# Sheet1.net
KiCad netlist of a schematic drawn in Altium Designer
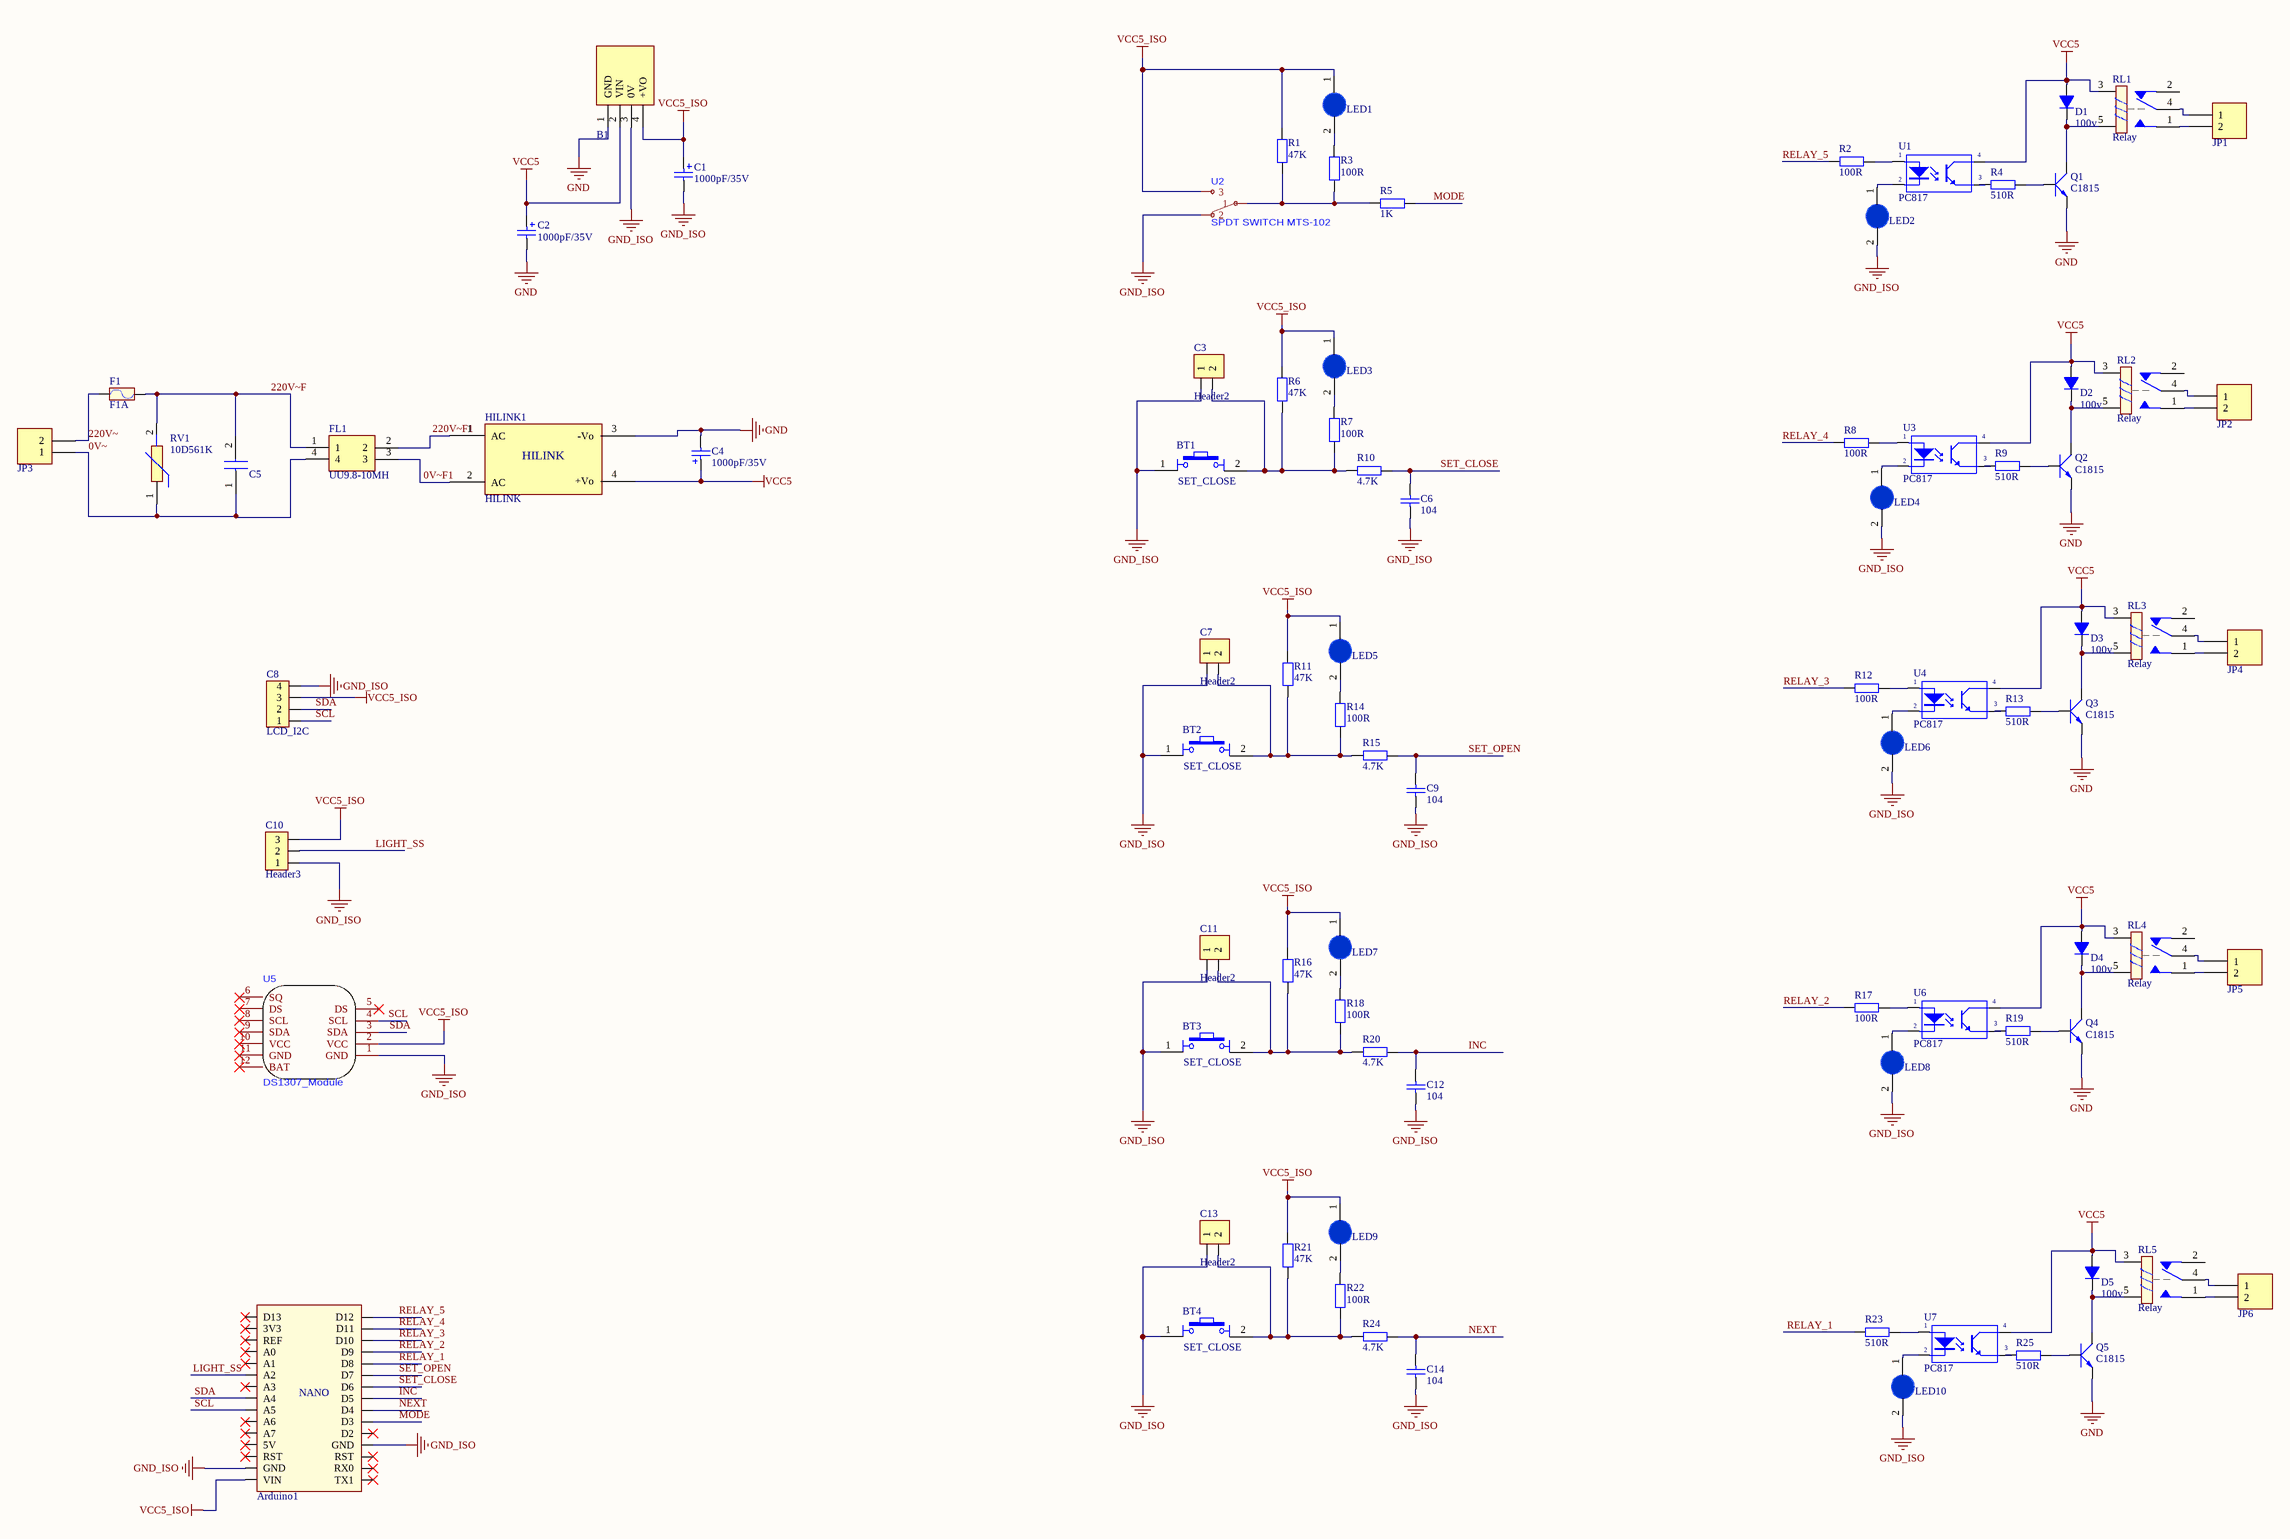
[diagram p0: Sheet1.SchDoc]

(export (version "E")
  (design (tool "Eeschema 10.0.6"))
  (components
    (comp (ref "Arduino1")
      (value "Arduino Nano")
      (footprint "Arduino Nano")
      (description "Arduino NANO")
      (libsource (lib "myLib_v1") (part "Arduino Nano"))
    )
    (comp (ref "B1")
      (value "B0505S1W")
      (footprint "B0505S1W")
      (description "Power Supply")
      (fields (field (name "MANUFACTURER_PART_NUMBER") "B0505S-1W"))
      (libsource (lib "myLib_v1") (part "B0505S1W"))
    )
    (comp (ref "BT1")
      (value "SET_CLOSE")
      (footprint "Nut Nhan 4 Chan Cam 6x6")
      (description "Nut Nhan 4 Chan 6x6mm")
      (libsource (lib "Altium_Lib_by_KhueNguyenCreator") (part "Nut Nhan 4 Chan Cam 6x6"))
    )
    (comp (ref "BT2")
      (value "SET_CLOSE")
      (footprint "Nut Nhan 4 Chan Cam 6x6")
      (description "Nut Nhan 4 Chan 6x6mm")
      (libsource (lib "Altium_Lib_by_KhueNguyenCreator") (part "Nut Nhan 4 Chan Cam 6x6"))
    )
    (comp (ref "BT3")
      (value "SET_CLOSE")
      (footprint "Nut Nhan 4 Chan Cam 6x6")
      (description "Nut Nhan 4 Chan 6x6mm")
      (libsource (lib "Altium_Lib_by_KhueNguyenCreator") (part "Nut Nhan 4 Chan Cam 6x6"))
    )
    (comp (ref "BT4")
      (value "SET_CLOSE")
      (footprint "Nut Nhan 4 Chan Cam 6x6")
      (description "Nut Nhan 4 Chan 6x6mm")
      (libsource (lib "Altium_Lib_by_KhueNguyenCreator") (part "Nut Nhan 4 Chan Cam 6x6"))
    )
    (comp (ref "C1")
      (value "1000pF/35V")
      (footprint "CP2/5")
      (description "Polarized Capacitor (Surface Mount)")
      (fields (field (name "Comment") "Cap Pol3") (field (name "PUBLISHER") "Altium Limited"))
      (libsource (lib "myLib_v1") (part "Cap Pol3"))
    )
    (comp (ref "C2")
      (value "1000pF/35V")
      (footprint "CP2/5")
      (description "Polarized Capacitor (Surface Mount)")
      (fields (field (name "Comment") "Cap Pol3") (field (name "PUBLISHER") "Altium Limited"))
      (libsource (lib "myLib_v1") (part "Cap Pol3"))
    )
    (comp (ref "C3")
      (value "Header2")
      (footprint "Header2")
      (description "Header IDC, 2 x 1 Pin Vertical 2.54mm Pitch (Non-Boxed, Male)")
      (fields
        (field (name "MANUFACTURER") "Würth Elektronik eiSos GmbH")
        (field (name "PARTNO") "613002143121")
        (field (name "CREATED BY") "Karrer Zheng")
      )
      (libsource (lib "myLib_v1") (part "Header2"))
    )
    (comp (ref "C4")
      (value "1000pF/35V")
      (footprint "CP2/5")
      (description "Polarized Capacitor (Surface Mount)")
      (fields (field (name "Comment") "Cap Pol3") (field (name "PUBLISHER") "Altium Limited"))
      (libsource (lib "myLib_v1") (part "Cap Pol3"))
    )
    (comp (ref "C5")
      (value "R46KF3100JMP0K")
      (footprint "R46KF3100JMP0K")
      (description "Capacitor")
      (fields (field (name "MOUSER PART NUMBER") "80-R46KF3100JMP0K"))
      (libsource (lib "myLib_v1") (part "R46KF3100JMP0K"))
    )
    (comp (ref "C6")
      (value "104")
      (footprint "tu gom")
      (description "Cắm")
      (libsource (lib "Altium_Lib_by_KhueNguyenCreator") (part "Tu gom 104 50V"))
    )
    (comp (ref "C7")
      (value "Header2")
      (footprint "Header2")
      (description "Header IDC, 2 x 1 Pin Vertical 2.54mm Pitch (Non-Boxed, Male)")
      (fields
        (field (name "MANUFACTURER") "Würth Elektronik eiSos GmbH")
        (field (name "PARTNO") "613002143121")
        (field (name "CREATED BY") "Karrer Zheng")
      )
      (libsource (lib "myLib_v1") (part "Header2"))
    )
    (comp (ref "C8")
      (value "LCD_I2C")
      (footprint "Header4")
      (description "Header IDC, 4 x 1 Pin Vertical 2.54mm Pitch (Non-Boxed, Male)")
      (fields
        (field (name "MANUFACTURER") "Würth Elektronik eiSos GmbH")
        (field (name "PARTNO") "613002143121")
        (field (name "CREATED BY") "Karrer Zheng")
      )
      (libsource (lib "myLib_v1") (part "Header4"))
    )
    (comp (ref "C9")
      (value "104")
      (footprint "tu gom")
      (description "Cắm")
      (libsource (lib "Altium_Lib_by_KhueNguyenCreator") (part "Tu gom 104 50V"))
    )
    (comp (ref "C10")
      (value "Header3")
      (footprint "Header3")
      (description "Header IDC, 3 x 1 Pin Vertical 2.54mm Pitch (Non-Boxed, Male)")
      (fields
        (field (name "MANUFACTURER") "Würth Elektronik eiSos GmbH")
        (field (name "PARTNO") "613002143121")
        (field (name "CREATED BY") "Karrer Zheng")
      )
      (libsource (lib "myLib_v1") (part "Header3"))
    )
    (comp (ref "C11")
      (value "Header2")
      (footprint "Header2")
      (description "Header IDC, 2 x 1 Pin Vertical 2.54mm Pitch (Non-Boxed, Male)")
      (fields
        (field (name "MANUFACTURER") "Würth Elektronik eiSos GmbH")
        (field (name "PARTNO") "613002143121")
        (field (name "CREATED BY") "Karrer Zheng")
      )
      (libsource (lib "myLib_v1") (part "Header2"))
    )
    (comp (ref "C12")
      (value "104")
      (footprint "tu gom")
      (description "Cắm")
      (libsource (lib "Altium_Lib_by_KhueNguyenCreator") (part "Tu gom 104 50V"))
    )
    (comp (ref "C13")
      (value "Header2")
      (footprint "Header2")
      (description "Header IDC, 2 x 1 Pin Vertical 2.54mm Pitch (Non-Boxed, Male)")
      (fields
        (field (name "MANUFACTURER") "Würth Elektronik eiSos GmbH")
        (field (name "PARTNO") "613002143121")
        (field (name "CREATED BY") "Karrer Zheng")
      )
      (libsource (lib "myLib_v1") (part "Header2"))
    )
    (comp (ref "C14")
      (value "104")
      (footprint "tu gom")
      (description "Cắm")
      (libsource (lib "Altium_Lib_by_KhueNguyenCreator") (part "Tu gom 104 50V"))
    )
    (comp (ref "D1")
      (value "100v")
      (footprint "DIODE 0.5A")
      (description "Cắm")
      (libsource (lib "Altium_Lib_by_KhueNguyenCreator") (part "Diode 1N4148"))
    )
    (comp (ref "D2")
      (value "100v")
      (footprint "DIODE 0.5A")
      (description "Cắm")
      (libsource (lib "Altium_Lib_by_KhueNguyenCreator") (part "Diode 1N4148"))
    )
    (comp (ref "D3")
      (value "100v")
      (footprint "DIODE 0.5A")
      (description "Cắm")
      (libsource (lib "Altium_Lib_by_KhueNguyenCreator") (part "Diode 1N4148"))
    )
    (comp (ref "D4")
      (value "100v")
      (footprint "DIODE 0.5A")
      (description "Cắm")
      (libsource (lib "Altium_Lib_by_KhueNguyenCreator") (part "Diode 1N4148"))
    )
    (comp (ref "D5")
      (value "100v")
      (footprint "DIODE 0.5A")
      (description "Cắm")
      (libsource (lib "Altium_Lib_by_KhueNguyenCreator") (part "Diode 1N4148"))
    )
    (comp (ref "F1")
      (value "F1A")
      (footprint "Fuse")
      (description "Fuse")
      (fields (field (name "DESIGNED BY") "VanDungEvn"))
      (libsource (lib "myLib_v1") (part "Fuse"))
    )
    (comp (ref "FL1")
      (value "UU9.8-10MH")
      (footprint "UU9810MH")
      (description "Filter")
      (libsource (lib "myLib_v1") (part "UU9.8-10MH"))
    )
    (comp (ref "HILINK1")
      (value "HILINK")
      (footprint "HILINK_1W")
      (libsource (lib "myLib_v1") (part "HILINK"))
    )
    (comp (ref "JP1")
      (value "Header 2_1")
      (footprint "HED2")
      (description "Header, 2-Pin")
      (fields (field (name "MANUFACTURER") "Generic Components"))
      (libsource (lib "myLib_v1") (part "Header 2_1"))
    )
    (comp (ref "JP2")
      (value "Header 2_1")
      (footprint "HED2")
      (description "Header, 2-Pin")
      (fields (field (name "MANUFACTURER") "Generic Components"))
      (libsource (lib "myLib_v1") (part "Header 2_1"))
    )
    (comp (ref "JP3")
      (value "Header 2_1")
      (footprint "HED2")
      (description "Header, 2-Pin")
      (fields (field (name "MANUFACTURER") "Generic Components"))
      (libsource (lib "") (part "Header 2_1_1"))
    )
    (comp (ref "JP4")
      (value "Header 2_1")
      (footprint "HED2")
      (description "Header, 2-Pin")
      (fields (field (name "MANUFACTURER") "Generic Components"))
      (libsource (lib "myLib_v1") (part "Header 2_1"))
    )
    (comp (ref "JP5")
      (value "Header 2_1")
      (footprint "HED2")
      (description "Header, 2-Pin")
      (fields (field (name "MANUFACTURER") "Generic Components"))
      (libsource (lib "myLib_v1") (part "Header 2_1"))
    )
    (comp (ref "JP6")
      (value "Header 2_1")
      (footprint "HED2")
      (description "Header, 2-Pin")
      (fields (field (name "MANUFACTURER") "Generic Components"))
      (libsource (lib "myLib_v1") (part "Header 2_1"))
    )
    (comp (ref "LED1")
      (value "LED 3mm")
      (footprint "LED-3MM-BLUE")
      (description "Cắm")
      (libsource (lib "myLib_v1") (part "LED 3mm Xanh Duong"))
    )
    (comp (ref "LED2")
      (value "LED 3mm")
      (footprint "LED-3MM-BLUE")
      (description "Cắm")
      (libsource (lib "myLib_v1") (part "LED 3mm Xanh Duong"))
    )
    (comp (ref "LED3")
      (value "LED 3mm")
      (footprint "LED-3MM-BLUE")
      (description "Cắm")
      (libsource (lib "myLib_v1") (part "LED 3mm Xanh Duong"))
    )
    (comp (ref "LED4")
      (value "LED 3mm")
      (footprint "LED-3MM-BLUE")
      (description "Cắm")
      (libsource (lib "myLib_v1") (part "LED 3mm Xanh Duong"))
    )
    (comp (ref "LED5")
      (value "LED 3mm")
      (footprint "LED-3MM-BLUE")
      (description "Cắm")
      (libsource (lib "myLib_v1") (part "LED 3mm Xanh Duong"))
    )
    (comp (ref "LED6")
      (value "LED 3mm")
      (footprint "LED-3MM-BLUE")
      (description "Cắm")
      (libsource (lib "myLib_v1") (part "LED 3mm Xanh Duong"))
    )
    (comp (ref "LED7")
      (value "LED 3mm")
      (footprint "LED-3MM-BLUE")
      (description "Cắm")
      (libsource (lib "myLib_v1") (part "LED 3mm Xanh Duong"))
    )
    (comp (ref "LED8")
      (value "LED 3mm")
      (footprint "LED-3MM-BLUE")
      (description "Cắm")
      (libsource (lib "myLib_v1") (part "LED 3mm Xanh Duong"))
    )
    (comp (ref "LED9")
      (value "LED 3mm")
      (footprint "LED-3MM-BLUE")
      (description "Cắm")
      (libsource (lib "myLib_v1") (part "LED 3mm Xanh Duong"))
    )
    (comp (ref "LED10")
      (value "LED 3mm")
      (footprint "LED-3MM-BLUE")
      (description "Cắm")
      (libsource (lib "myLib_v1") (part "LED 3mm Xanh Duong"))
    )
    (comp (ref "Q1")
      (value "C1815")
      (footprint "C1815_cam")
      (description "NPN 600mW, ECB")
      (libsource (lib "myLib_v1") (part "C1815"))
    )
    (comp (ref "Q2")
      (value "C1815")
      (footprint "C1815_cam")
      (description "NPN 600mW, ECB")
      (libsource (lib "myLib_v1") (part "C1815"))
    )
    (comp (ref "Q3")
      (value "C1815")
      (footprint "C1815_cam")
      (description "NPN 600mW, ECB")
      (libsource (lib "myLib_v1") (part "C1815"))
    )
    (comp (ref "Q4")
      (value "C1815")
      (footprint "C1815_cam")
      (description "NPN 600mW, ECB")
      (libsource (lib "myLib_v1") (part "C1815"))
    )
    (comp (ref "Q5")
      (value "C1815")
      (footprint "C1815_cam")
      (description "NPN 600mW, ECB")
      (libsource (lib "myLib_v1") (part "C1815"))
    )
    (comp (ref "R1")
      (value "47K")
      (footprint "R1/4W")
      (description "Resistor 1/4W")
      (libsource (lib "myLib_v1") (part "R1/4W"))
    )
    (comp (ref "R2")
      (value "100R")
      (footprint "R1/4W")
      (description "Resistor 1/4W")
      (libsource (lib "myLib_v1") (part "R1/4W"))
    )
    (comp (ref "R3")
      (value "100R")
      (footprint "R1/4W")
      (description "Resistor 1/4W")
      (libsource (lib "myLib_v1") (part "R1/4W"))
    )
    (comp (ref "R4")
      (value "510R")
      (footprint "R1/4W")
      (description "Resistor 1/4W")
      (libsource (lib "myLib_v1") (part "R1/4W"))
    )
    (comp (ref "R5")
      (value "1K")
      (footprint "R1/4W")
      (description "Resistor 1/4W")
      (libsource (lib "myLib_v1") (part "R1/4W"))
    )
    (comp (ref "R6")
      (value "47K")
      (footprint "R1/4W")
      (description "Resistor 1/4W")
      (libsource (lib "myLib_v1") (part "R1/4W"))
    )
    (comp (ref "R7")
      (value "100R")
      (footprint "R1/4W")
      (description "Resistor 1/4W")
      (libsource (lib "myLib_v1") (part "R1/4W"))
    )
    (comp (ref "R8")
      (value "100R")
      (footprint "R1/4W")
      (description "Resistor 1/4W")
      (libsource (lib "myLib_v1") (part "R1/4W"))
    )
    (comp (ref "R9")
      (value "510R")
      (footprint "R1/4W")
      (description "Resistor 1/4W")
      (libsource (lib "myLib_v1") (part "R1/4W"))
    )
    (comp (ref "R10")
      (value "4.7K")
      (footprint "R1/4W")
      (description "Resistor 1/4W")
      (libsource (lib "myLib_v1") (part "R1/4W"))
    )
    (comp (ref "R11")
      (value "47K")
      (footprint "R1/4W")
      (description "Resistor 1/4W")
      (libsource (lib "myLib_v1") (part "R1/4W"))
    )
    (comp (ref "R12")
      (value "100R")
      (footprint "R1/4W")
      (description "Resistor 1/4W")
      (libsource (lib "myLib_v1") (part "R1/4W"))
    )
    (comp (ref "R13")
      (value "510R")
      (footprint "R1/4W")
      (description "Resistor 1/4W")
      (libsource (lib "myLib_v1") (part "R1/4W"))
    )
    (comp (ref "R14")
      (value "100R")
      (footprint "R1/4W")
      (description "Resistor 1/4W")
      (libsource (lib "myLib_v1") (part "R1/4W"))
    )
    (comp (ref "R15")
      (value "4.7K")
      (footprint "R1/4W")
      (description "Resistor 1/4W")
      (libsource (lib "myLib_v1") (part "R1/4W"))
    )
    (comp (ref "R16")
      (value "47K")
      (footprint "R1/4W")
      (description "Resistor 1/4W")
      (libsource (lib "myLib_v1") (part "R1/4W"))
    )
    (comp (ref "R17")
      (value "100R")
      (footprint "R1/4W")
      (description "Resistor 1/4W")
      (libsource (lib "myLib_v1") (part "R1/4W"))
    )
    (comp (ref "R18")
      (value "100R")
      (footprint "R1/4W")
      (description "Resistor 1/4W")
      (libsource (lib "myLib_v1") (part "R1/4W"))
    )
    (comp (ref "R19")
      (value "510R")
      (footprint "R1/4W")
      (description "Resistor 1/4W")
      (libsource (lib "myLib_v1") (part "R1/4W"))
    )
    (comp (ref "R20")
      (value "4.7K")
      (footprint "R1/4W")
      (description "Resistor 1/4W")
      (libsource (lib "myLib_v1") (part "R1/4W"))
    )
    (comp (ref "R21")
      (value "47K")
      (footprint "R1/4W")
      (description "Resistor 1/4W")
      (libsource (lib "myLib_v1") (part "R1/4W"))
    )
    (comp (ref "R22")
      (value "100R")
      (footprint "R1/4W")
      (description "Resistor 1/4W")
      (libsource (lib "myLib_v1") (part "R1/4W"))
    )
    (comp (ref "R23")
      (value "510R")
      (footprint "R1/4W")
      (description "Resistor 1/4W")
      (libsource (lib "myLib_v1") (part "R1/4W"))
    )
    (comp (ref "R24")
      (value "4.7K")
      (footprint "R1/4W")
      (description "Resistor 1/4W")
      (libsource (lib "myLib_v1") (part "R1/4W"))
    )
    (comp (ref "R25")
      (value "510R")
      (footprint "R1/4W")
      (description "Resistor 1/4W")
      (libsource (lib "myLib_v1") (part "R1/4W"))
    )
    (comp (ref "RL1")
      (value "Relay")
      (footprint "RELAY_SRA_05VDC_CL")
      (description "Relay 5 Chan")
      (libsource (lib "myLib_v1") (part "RL_SRA-05VDC-CL"))
    )
    (comp (ref "RL2")
      (value "Relay")
      (footprint "RELAY_SRA_05VDC_CL")
      (description "Relay 5 Chan")
      (libsource (lib "myLib_v1") (part "RL_SRA-05VDC-CL"))
    )
    (comp (ref "RL3")
      (value "Relay")
      (footprint "RELAY_SRA_05VDC_CL")
      (description "Relay 5 Chan")
      (libsource (lib "myLib_v1") (part "RL_SRA-05VDC-CL"))
    )
    (comp (ref "RL4")
      (value "Relay")
      (footprint "RELAY_SRA_05VDC_CL")
      (description "Relay 5 Chan")
      (libsource (lib "myLib_v1") (part "RL_SRA-05VDC-CL"))
    )
    (comp (ref "RL5")
      (value "Relay")
      (footprint "RELAY_SRA_05VDC_CL")
      (description "Relay 5 Chan")
      (libsource (lib "myLib_v1") (part "RL_SRA-05VDC-CL"))
    )
    (comp (ref "RV1")
      (value "10D561K")
      (footprint "10D561K")
      (description "Varistor")
      (fields
        (field (name "MANUFACTURER_PART_NUMBER") "MOV-10D561K")
        (field (name "MOUSER PART NUMBER") "652-MOV-10D561K")
      )
      (libsource (lib "myLib_v1") (part "10D561K"))
    )
    (comp (ref "U1")
      (value "PC817")
      (footprint "DIP4/W0.3")
      (description "Single Opto")
      (libsource (lib "myLib_v1") (part "PC817"))
    )
    (comp (ref "U2")
      (value "SPDT SWITCH MTS-102")
      (footprint "SPDT SWITCH  MTS-102")
      (libsource (lib "myLib_v1") (part "SPDT SWITCH MTS-102"))
    )
    (comp (ref "U3")
      (value "PC817")
      (footprint "DIP4/W0.3")
      (description "Single Opto")
      (libsource (lib "myLib_v1") (part "PC817"))
    )
    (comp (ref "U4")
      (value "PC817")
      (footprint "DIP4/W0.3")
      (description "Single Opto")
      (libsource (lib "myLib_v1") (part "PC817"))
    )
    (comp (ref "U5")
      (value "DS1307_Module")
      (footprint "DS1307 MODULE")
      (libsource (lib "myLib_v1") (part "DS1307_Module"))
    )
    (comp (ref "U6")
      (value "PC817")
      (footprint "DIP4/W0.3")
      (description "Single Opto")
      (libsource (lib "myLib_v1") (part "PC817"))
    )
    (comp (ref "U7")
      (value "PC817")
      (footprint "DIP4/W0.3")
      (description "Single Opto")
      (libsource (lib "myLib_v1") (part "PC817"))
    )
  )
  (nets
    (net (code "1") (name "/0V~") (class "Default")
      (node (ref "C5") (pin "1") (pinfunction "1_1") (pintype "passive"))
      (node (ref "FL1") (pin "4") (pinfunction "4_4") (pintype "passive"))
      (node (ref "JP3") (pin "1") (pinfunction "1_1") (pintype "passive"))
      (node (ref "RV1") (pin "1") (pinfunction "1_1") (pintype "passive"))
    )
    (net (code "2") (name "/0V~F1") (class "Default")
      (node (ref "FL1") (pin "3") (pinfunction "3_3") (pintype "passive"))
      (node (ref "HILINK1") (pin "2") (pinfunction "AC_2") (pintype "passive"))
    )
    (net (code "3") (name "/220V~") (class "Default")
      (node (ref "F1") (pin "1") (pinfunction "1_1") (pintype "passive"))
      (node (ref "JP3") (pin "2") (pinfunction "2_2") (pintype "passive"))
    )
    (net (code "4") (name "/220V~F") (class "Default")
      (node (ref "C5") (pin "2") (pinfunction "2_2") (pintype "passive"))
      (node (ref "F1") (pin "2") (pinfunction "2_2") (pintype "passive"))
      (node (ref "FL1") (pin "1") (pinfunction "1_1") (pintype "passive"))
      (node (ref "RV1") (pin "2") (pinfunction "2_2") (pintype "passive"))
    )
    (net (code "5") (name "/220V~F1") (class "Default")
      (node (ref "FL1") (pin "2") (pinfunction "2_2") (pintype "passive"))
      (node (ref "HILINK1") (pin "1") (pinfunction "AC_1") (pintype "passive"))
    )
    (net (code "6") (name "/INC") (class "Default")
      (node (ref "Arduino1") (pin "D5") (pinfunction "D5_D5") (pintype "passive"))
      (node (ref "C12") (pin "1") (pinfunction "1_1") (pintype "passive"))
      (node (ref "R20") (pin "1") (pinfunction "1_1") (pintype "passive"))
    )
    (net (code "7") (name "/LIGHT_SS") (class "Default")
      (node (ref "Arduino1") (pin "A2") (pinfunction "A2_A2") (pintype "passive"))
      (node (ref "C10") (pin "2") (pinfunction "2_2") (pintype "passive"))
    )
    (net (code "8") (name "/MODE") (class "Default")
      (node (ref "Arduino1") (pin "D3") (pinfunction "D3_D3") (pintype "passive"))
      (node (ref "R5") (pin "1") (pinfunction "1_1") (pintype "passive"))
    )
    (net (code "9") (name "/NEXT") (class "Default")
      (node (ref "Arduino1") (pin "D4") (pinfunction "D4_D4") (pintype "passive"))
      (node (ref "C14") (pin "1") (pinfunction "1_1") (pintype "passive"))
      (node (ref "R24") (pin "1") (pinfunction "1_1") (pintype "passive"))
    )
    (net (code "10") (name "/RELAY_1") (class "Default")
      (node (ref "Arduino1") (pin "D8") (pinfunction "D8_D8") (pintype "passive"))
      (node (ref "R23") (pin "1") (pinfunction "1_1") (pintype "passive"))
    )
    (net (code "11") (name "/RELAY_2") (class "Default")
      (node (ref "Arduino1") (pin "D9") (pinfunction "D9_D9") (pintype "passive"))
      (node (ref "R17") (pin "1") (pinfunction "1_1") (pintype "passive"))
    )
    (net (code "12") (name "/RELAY_3") (class "Default")
      (node (ref "Arduino1") (pin "D10") (pinfunction "D10_D10") (pintype "passive"))
      (node (ref "R12") (pin "1") (pinfunction "1_1") (pintype "passive"))
    )
    (net (code "13") (name "/RELAY_4") (class "Default")
      (node (ref "Arduino1") (pin "D11") (pinfunction "D11_D11") (pintype "passive"))
      (node (ref "R8") (pin "1") (pinfunction "1_1") (pintype "passive"))
    )
    (net (code "14") (name "/RELAY_5") (class "Default")
      (node (ref "Arduino1") (pin "D12") (pinfunction "D12_D12") (pintype "passive"))
      (node (ref "R2") (pin "1") (pinfunction "1_1") (pintype "passive"))
    )
    (net (code "15") (name "/SCL") (class "Default")
      (node (ref "Arduino1") (pin "A5") (pinfunction "A5_A5") (pintype "passive"))
      (node (ref "C8") (pin "1") (pinfunction "1_1") (pintype "passive"))
      (node (ref "U5") (pin "4") (pinfunction "SCL_4") (pintype "passive"))
    )
    (net (code "16") (name "/SDA") (class "Default")
      (node (ref "Arduino1") (pin "A4") (pinfunction "A4_A4") (pintype "passive"))
      (node (ref "C8") (pin "2") (pinfunction "2_2") (pintype "passive"))
      (node (ref "U5") (pin "3") (pinfunction "SDA_3") (pintype "passive"))
    )
    (net (code "17") (name "/SET_CLOSE") (class "Default")
      (node (ref "Arduino1") (pin "D6") (pinfunction "D6_D6") (pintype "passive"))
      (node (ref "C6") (pin "1") (pinfunction "1_1") (pintype "passive"))
      (node (ref "R10") (pin "1") (pinfunction "1_1") (pintype "passive"))
    )
    (net (code "18") (name "/SET_OPEN") (class "Default")
      (node (ref "Arduino1") (pin "D7") (pinfunction "D7_D7") (pintype "passive"))
      (node (ref "C9") (pin "1") (pinfunction "1_1") (pintype "passive"))
      (node (ref "R15") (pin "1") (pinfunction "1_1") (pintype "passive"))
    )
    (net (code "19") (name "GND") (class "Default")
      (node (ref "B1") (pin "1") (pinfunction "GND_1") (pintype "passive"))
      (node (ref "C2") (pin "2") (pinfunction "2_2") (pintype "passive"))
      (node (ref "C4") (pin "2") (pinfunction "2_2") (pintype "passive"))
      (node (ref "HILINK1") (pin "3") (pinfunction "-Vo_3") (pintype "passive"))
      (node (ref "Q1") (pin "1") (pinfunction "E_1") (pintype "passive"))
      (node (ref "Q2") (pin "1") (pinfunction "E_1") (pintype "passive"))
      (node (ref "Q3") (pin "1") (pinfunction "E_1") (pintype "passive"))
      (node (ref "Q4") (pin "1") (pinfunction "E_1") (pintype "passive"))
      (node (ref "Q5") (pin "1") (pinfunction "E_1") (pintype "passive"))
    )
    (net (code "20") (name "GND_ISO") (class "Default")
      (node (ref "Arduino1") (pin "GND") (pinfunction "GND_GND") (pintype "passive"))
      (node (ref "B1") (pin "3") (pinfunction "0V_3") (pintype "passive"))
      (node (ref "BT1") (pin "1") (pintype "passive"))
      (node (ref "BT2") (pin "1") (pintype "passive"))
      (node (ref "BT3") (pin "1") (pintype "passive"))
      (node (ref "BT4") (pin "1") (pintype "passive"))
      (node (ref "C1") (pin "2") (pinfunction "2_2") (pintype "passive"))
      (node (ref "C10") (pin "1") (pinfunction "1_1") (pintype "passive"))
      (node (ref "C11") (pin "1") (pinfunction "1_1") (pintype "passive"))
      (node (ref "C12") (pin "2") (pinfunction "2_2") (pintype "passive"))
      (node (ref "C13") (pin "1") (pinfunction "1_1") (pintype "passive"))
      (node (ref "C14") (pin "2") (pinfunction "2_2") (pintype "passive"))
      (node (ref "C3") (pin "1") (pinfunction "1_1") (pintype "passive"))
      (node (ref "C6") (pin "2") (pinfunction "2_2") (pintype "passive"))
      (node (ref "C7") (pin "1") (pinfunction "1_1") (pintype "passive"))
      (node (ref "C8") (pin "4") (pinfunction "4_4") (pintype "passive"))
      (node (ref "C9") (pin "2") (pinfunction "2_2") (pintype "passive"))
      (node (ref "LED10") (pin "2") (pinfunction "K_2") (pintype "passive"))
      (node (ref "LED2") (pin "2") (pinfunction "K_2") (pintype "passive"))
      (node (ref "LED4") (pin "2") (pinfunction "K_2") (pintype "passive"))
      (node (ref "LED6") (pin "2") (pinfunction "K_2") (pintype "passive"))
      (node (ref "LED8") (pin "2") (pinfunction "K_2") (pintype "passive"))
      (node (ref "U2") (pin "2") (pinfunction "2_2") (pintype "passive"))
      (node (ref "U5") (pin "1") (pinfunction "GND_1") (pintype "passive"))
    )
    (net (code "21") (name "Net-(BT1-Pad2)") (class "Default")
      (node (ref "BT1") (pin "2") (pintype "passive"))
      (node (ref "C3") (pin "2") (pinfunction "2_2") (pintype "passive"))
      (node (ref "R10") (pin "2") (pinfunction "2_2") (pintype "passive"))
      (node (ref "R6") (pin "1") (pinfunction "1_1") (pintype "passive"))
      (node (ref "R7") (pin "1") (pinfunction "1_1") (pintype "passive"))
    )
    (net (code "22") (name "Net-(BT2-Pad2)") (class "Default")
      (node (ref "BT2") (pin "2") (pintype "passive"))
      (node (ref "C7") (pin "2") (pinfunction "2_2") (pintype "passive"))
      (node (ref "R11") (pin "1") (pinfunction "1_1") (pintype "passive"))
      (node (ref "R14") (pin "1") (pinfunction "1_1") (pintype "passive"))
      (node (ref "R15") (pin "2") (pinfunction "2_2") (pintype "passive"))
    )
    (net (code "23") (name "Net-(BT3-Pad2)") (class "Default")
      (node (ref "BT3") (pin "2") (pintype "passive"))
      (node (ref "C11") (pin "2") (pinfunction "2_2") (pintype "passive"))
      (node (ref "R16") (pin "1") (pinfunction "1_1") (pintype "passive"))
      (node (ref "R18") (pin "1") (pinfunction "1_1") (pintype "passive"))
      (node (ref "R20") (pin "2") (pinfunction "2_2") (pintype "passive"))
    )
    (net (code "24") (name "Net-(BT4-Pad2)") (class "Default")
      (node (ref "BT4") (pin "2") (pintype "passive"))
      (node (ref "C13") (pin "2") (pinfunction "2_2") (pintype "passive"))
      (node (ref "R21") (pin "1") (pinfunction "1_1") (pintype "passive"))
      (node (ref "R22") (pin "1") (pinfunction "1_1") (pintype "passive"))
      (node (ref "R24") (pin "2") (pinfunction "2_2") (pintype "passive"))
    )
    (net (code "25") (name "Net-(D1-K)") (class "Default")
      (node (ref "D1") (pin "2") (pinfunction "K_2") (pintype "passive"))
      (node (ref "Q1") (pin "2") (pinfunction "C_2") (pintype "passive"))
      (node (ref "RL1") (pin "5") (pinfunction "5_5") (pintype "passive"))
    )
    (net (code "26") (name "Net-(D2-K)") (class "Default")
      (node (ref "D2") (pin "2") (pinfunction "K_2") (pintype "passive"))
      (node (ref "Q2") (pin "2") (pinfunction "C_2") (pintype "passive"))
      (node (ref "RL2") (pin "5") (pinfunction "5_5") (pintype "passive"))
    )
    (net (code "27") (name "Net-(D3-K)") (class "Default")
      (node (ref "D3") (pin "2") (pinfunction "K_2") (pintype "passive"))
      (node (ref "Q3") (pin "2") (pinfunction "C_2") (pintype "passive"))
      (node (ref "RL3") (pin "5") (pinfunction "5_5") (pintype "passive"))
    )
    (net (code "28") (name "Net-(D4-K)") (class "Default")
      (node (ref "D4") (pin "2") (pinfunction "K_2") (pintype "passive"))
      (node (ref "Q4") (pin "2") (pinfunction "C_2") (pintype "passive"))
      (node (ref "RL4") (pin "5") (pinfunction "5_5") (pintype "passive"))
    )
    (net (code "29") (name "Net-(D5-K)") (class "Default")
      (node (ref "D5") (pin "2") (pinfunction "K_2") (pintype "passive"))
      (node (ref "Q5") (pin "2") (pinfunction "C_2") (pintype "passive"))
      (node (ref "RL5") (pin "5") (pinfunction "5_5") (pintype "passive"))
    )
    (net (code "30") (name "Net-(JP1-Pad1)") (class "Default")
      (node (ref "JP1") (pin "1") (pinfunction "1_1") (pintype "passive"))
      (node (ref "RL1") (pin "4") (pinfunction "4_4") (pintype "passive"))
    )
    (net (code "31") (name "Net-(JP1-Pad2)") (class "Default")
      (node (ref "JP1") (pin "2") (pinfunction "2_2") (pintype "passive"))
      (node (ref "RL1") (pin "1") (pinfunction "1_1") (pintype "passive"))
    )
    (net (code "32") (name "Net-(JP2-Pad1)") (class "Default")
      (node (ref "JP2") (pin "1") (pinfunction "1_1") (pintype "passive"))
      (node (ref "RL2") (pin "4") (pinfunction "4_4") (pintype "passive"))
    )
    (net (code "33") (name "Net-(JP2-Pad2)") (class "Default")
      (node (ref "JP2") (pin "2") (pinfunction "2_2") (pintype "passive"))
      (node (ref "RL2") (pin "1") (pinfunction "1_1") (pintype "passive"))
    )
    (net (code "34") (name "Net-(JP4-Pad1)") (class "Default")
      (node (ref "JP4") (pin "1") (pinfunction "1_1") (pintype "passive"))
      (node (ref "RL3") (pin "4") (pinfunction "4_4") (pintype "passive"))
    )
    (net (code "35") (name "Net-(JP4-Pad2)") (class "Default")
      (node (ref "JP4") (pin "2") (pinfunction "2_2") (pintype "passive"))
      (node (ref "RL3") (pin "1") (pinfunction "1_1") (pintype "passive"))
    )
    (net (code "36") (name "Net-(JP5-Pad1)") (class "Default")
      (node (ref "JP5") (pin "1") (pinfunction "1_1") (pintype "passive"))
      (node (ref "RL4") (pin "4") (pinfunction "4_4") (pintype "passive"))
    )
    (net (code "37") (name "Net-(JP5-Pad2)") (class "Default")
      (node (ref "JP5") (pin "2") (pinfunction "2_2") (pintype "passive"))
      (node (ref "RL4") (pin "1") (pinfunction "1_1") (pintype "passive"))
    )
    (net (code "38") (name "Net-(JP6-Pad1)") (class "Default")
      (node (ref "JP6") (pin "1") (pinfunction "1_1") (pintype "passive"))
      (node (ref "RL5") (pin "4") (pinfunction "4_4") (pintype "passive"))
    )
    (net (code "39") (name "Net-(JP6-Pad2)") (class "Default")
      (node (ref "JP6") (pin "2") (pinfunction "2_2") (pintype "passive"))
      (node (ref "RL5") (pin "1") (pinfunction "1_1") (pintype "passive"))
    )
    (net (code "40") (name "Net-(LED1-K)") (class "Default")
      (node (ref "LED1") (pin "2") (pinfunction "K_2") (pintype "passive"))
      (node (ref "R3") (pin "2") (pinfunction "2_2") (pintype "passive"))
    )
    (net (code "41") (name "Net-(LED2-A)") (class "Default")
      (node (ref "LED2") (pin "1") (pinfunction "A_1") (pintype "passive"))
      (node (ref "U1") (pin "2") (pinfunction "K_2") (pintype "passive"))
    )
    (net (code "42") (name "Net-(LED3-K)") (class "Default")
      (node (ref "LED3") (pin "2") (pinfunction "K_2") (pintype "passive"))
      (node (ref "R7") (pin "2") (pinfunction "2_2") (pintype "passive"))
    )
    (net (code "43") (name "Net-(LED4-A)") (class "Default")
      (node (ref "LED4") (pin "1") (pinfunction "A_1") (pintype "passive"))
      (node (ref "U3") (pin "2") (pinfunction "K_2") (pintype "passive"))
    )
    (net (code "44") (name "Net-(LED5-K)") (class "Default")
      (node (ref "LED5") (pin "2") (pinfunction "K_2") (pintype "passive"))
      (node (ref "R14") (pin "2") (pinfunction "2_2") (pintype "passive"))
    )
    (net (code "45") (name "Net-(LED6-A)") (class "Default")
      (node (ref "LED6") (pin "1") (pinfunction "A_1") (pintype "passive"))
      (node (ref "U4") (pin "2") (pinfunction "K_2") (pintype "passive"))
    )
    (net (code "46") (name "Net-(LED7-K)") (class "Default")
      (node (ref "LED7") (pin "2") (pinfunction "K_2") (pintype "passive"))
      (node (ref "R18") (pin "2") (pinfunction "2_2") (pintype "passive"))
    )
    (net (code "47") (name "Net-(LED8-A)") (class "Default")
      (node (ref "LED8") (pin "1") (pinfunction "A_1") (pintype "passive"))
      (node (ref "U6") (pin "2") (pinfunction "K_2") (pintype "passive"))
    )
    (net (code "48") (name "Net-(LED9-K)") (class "Default")
      (node (ref "LED9") (pin "2") (pinfunction "K_2") (pintype "passive"))
      (node (ref "R22") (pin "2") (pinfunction "2_2") (pintype "passive"))
    )
    (net (code "49") (name "Net-(LED10-A)") (class "Default")
      (node (ref "LED10") (pin "1") (pinfunction "A_1") (pintype "passive"))
      (node (ref "U7") (pin "2") (pinfunction "K_2") (pintype "passive"))
    )
    (net (code "50") (name "Net-(Q1-B)") (class "Default")
      (node (ref "Q1") (pin "3") (pinfunction "B_3") (pintype "passive"))
      (node (ref "R4") (pin "2") (pinfunction "2_2") (pintype "passive"))
    )
    (net (code "51") (name "Net-(Q2-B)") (class "Default")
      (node (ref "Q2") (pin "3") (pinfunction "B_3") (pintype "passive"))
      (node (ref "R9") (pin "2") (pinfunction "2_2") (pintype "passive"))
    )
    (net (code "52") (name "Net-(Q3-B)") (class "Default")
      (node (ref "Q3") (pin "3") (pinfunction "B_3") (pintype "passive"))
      (node (ref "R13") (pin "2") (pinfunction "2_2") (pintype "passive"))
    )
    (net (code "53") (name "Net-(Q4-B)") (class "Default")
      (node (ref "Q4") (pin "3") (pinfunction "B_3") (pintype "passive"))
      (node (ref "R19") (pin "2") (pinfunction "2_2") (pintype "passive"))
    )
    (net (code "54") (name "Net-(Q5-B)") (class "Default")
      (node (ref "Q5") (pin "3") (pinfunction "B_3") (pintype "passive"))
      (node (ref "R25") (pin "2") (pinfunction "2_2") (pintype "passive"))
    )
    (net (code "55") (name "Net-(R1-Pad1)") (class "Default")
      (node (ref "R1") (pin "1") (pinfunction "1_1") (pintype "passive"))
      (node (ref "R3") (pin "1") (pinfunction "1_1") (pintype "passive"))
      (node (ref "R5") (pin "2") (pinfunction "2_2") (pintype "passive"))
      (node (ref "U2") (pin "1") (pinfunction "1_1") (pintype "passive"))
    )
    (net (code "56") (name "Net-(U1-A)") (class "Default")
      (node (ref "R2") (pin "2") (pinfunction "2_2") (pintype "passive"))
      (node (ref "U1") (pin "1") (pinfunction "A_1") (pintype "passive"))
    )
    (net (code "57") (name "Net-(U1-E)") (class "Default")
      (node (ref "R4") (pin "1") (pinfunction "1_1") (pintype "passive"))
      (node (ref "U1") (pin "3") (pinfunction "E_3") (pintype "passive"))
    )
    (net (code "58") (name "Net-(U3-A)") (class "Default")
      (node (ref "R8") (pin "2") (pinfunction "2_2") (pintype "passive"))
      (node (ref "U3") (pin "1") (pinfunction "A_1") (pintype "passive"))
    )
    (net (code "59") (name "Net-(U3-E)") (class "Default")
      (node (ref "R9") (pin "1") (pinfunction "1_1") (pintype "passive"))
      (node (ref "U3") (pin "3") (pinfunction "E_3") (pintype "passive"))
    )
    (net (code "60") (name "Net-(U4-A)") (class "Default")
      (node (ref "R12") (pin "2") (pinfunction "2_2") (pintype "passive"))
      (node (ref "U4") (pin "1") (pinfunction "A_1") (pintype "passive"))
    )
    (net (code "61") (name "Net-(U4-E)") (class "Default")
      (node (ref "R13") (pin "1") (pinfunction "1_1") (pintype "passive"))
      (node (ref "U4") (pin "3") (pinfunction "E_3") (pintype "passive"))
    )
    (net (code "62") (name "Net-(U6-A)") (class "Default")
      (node (ref "R17") (pin "2") (pinfunction "2_2") (pintype "passive"))
      (node (ref "U6") (pin "1") (pinfunction "A_1") (pintype "passive"))
    )
    (net (code "63") (name "Net-(U6-E)") (class "Default")
      (node (ref "R19") (pin "1") (pinfunction "1_1") (pintype "passive"))
      (node (ref "U6") (pin "3") (pinfunction "E_3") (pintype "passive"))
    )
    (net (code "64") (name "Net-(U7-A)") (class "Default")
      (node (ref "R23") (pin "2") (pinfunction "2_2") (pintype "passive"))
      (node (ref "U7") (pin "1") (pinfunction "A_1") (pintype "passive"))
    )
    (net (code "65") (name "Net-(U7-E)") (class "Default")
      (node (ref "R25") (pin "1") (pinfunction "1_1") (pintype "passive"))
      (node (ref "U7") (pin "3") (pinfunction "E_3") (pintype "passive"))
    )
    (net (code "66") (name "VCC5") (class "Default")
      (node (ref "B1") (pin "2") (pinfunction "VIN_2") (pintype "passive"))
      (node (ref "C2") (pin "1") (pinfunction "1_1") (pintype "passive"))
      (node (ref "C4") (pin "1") (pinfunction "1_1") (pintype "passive"))
      (node (ref "D1") (pin "1") (pinfunction "A_1") (pintype "passive"))
      (node (ref "D2") (pin "1") (pinfunction "A_1") (pintype "passive"))
      (node (ref "D3") (pin "1") (pinfunction "A_1") (pintype "passive"))
      (node (ref "D4") (pin "1") (pinfunction "A_1") (pintype "passive"))
      (node (ref "D5") (pin "1") (pinfunction "A_1") (pintype "passive"))
      (node (ref "HILINK1") (pin "4") (pinfunction "+Vo_4") (pintype "passive"))
      (node (ref "RL1") (pin "3") (pinfunction "3_3") (pintype "passive"))
      (node (ref "RL2") (pin "3") (pinfunction "3_3") (pintype "passive"))
      (node (ref "RL3") (pin "3") (pinfunction "3_3") (pintype "passive"))
      (node (ref "RL4") (pin "3") (pinfunction "3_3") (pintype "passive"))
      (node (ref "RL5") (pin "3") (pinfunction "3_3") (pintype "passive"))
      (node (ref "U1") (pin "4") (pinfunction "C_4") (pintype "passive"))
      (node (ref "U3") (pin "4") (pinfunction "C_4") (pintype "passive"))
      (node (ref "U4") (pin "4") (pinfunction "C_4") (pintype "passive"))
      (node (ref "U6") (pin "4") (pinfunction "C_4") (pintype "passive"))
      (node (ref "U7") (pin "4") (pinfunction "C_4") (pintype "passive"))
    )
    (net (code "67") (name "VCC5_ISO") (class "Default")
      (node (ref "Arduino1") (pin "VIN") (pinfunction "VIN_VIN") (pintype "passive"))
      (node (ref "B1") (pin "4") (pinfunction "+VO_4") (pintype "passive"))
      (node (ref "C1") (pin "1") (pinfunction "1_1") (pintype "passive"))
      (node (ref "C10") (pin "3") (pinfunction "3_3") (pintype "passive"))
      (node (ref "C8") (pin "3") (pinfunction "3_3") (pintype "passive"))
      (node (ref "LED1") (pin "1") (pinfunction "A_1") (pintype "passive"))
      (node (ref "LED3") (pin "1") (pinfunction "A_1") (pintype "passive"))
      (node (ref "LED5") (pin "1") (pinfunction "A_1") (pintype "passive"))
      (node (ref "LED7") (pin "1") (pinfunction "A_1") (pintype "passive"))
      (node (ref "LED9") (pin "1") (pinfunction "A_1") (pintype "passive"))
      (node (ref "R1") (pin "2") (pinfunction "2_2") (pintype "passive"))
      (node (ref "R11") (pin "2") (pinfunction "2_2") (pintype "passive"))
      (node (ref "R16") (pin "2") (pinfunction "2_2") (pintype "passive"))
      (node (ref "R21") (pin "2") (pinfunction "2_2") (pintype "passive"))
      (node (ref "R6") (pin "2") (pinfunction "2_2") (pintype "passive"))
      (node (ref "U2") (pin "3") (pinfunction "3_3") (pintype "passive"))
      (node (ref "U5") (pin "2") (pinfunction "VCC_2") (pintype "passive"))
    )
    (net (code "68") (name "unconnected-(Arduino1-Pad3V3)") (class "Default")
      (node (ref "Arduino1") (pin "3V3") (pinfunction "3V3_3V3") (pintype "passive+no_connect"))
    )
    (net (code "69") (name "unconnected-(Arduino1-Pad5V)") (class "Default")
      (node (ref "Arduino1") (pin "5V") (pinfunction "5V_5V") (pintype "passive+no_connect"))
    )
    (net (code "70") (name "unconnected-(Arduino1-PadA0)") (class "Default")
      (node (ref "Arduino1") (pin "A0") (pinfunction "A0_A0") (pintype "passive+no_connect"))
    )
    (net (code "71") (name "unconnected-(Arduino1-PadA1)") (class "Default")
      (node (ref "Arduino1") (pin "A1") (pinfunction "A1_A1") (pintype "passive+no_connect"))
    )
    (net (code "72") (name "unconnected-(Arduino1-PadA3)") (class "Default")
      (node (ref "Arduino1") (pin "A3") (pinfunction "A3_A3") (pintype "passive+no_connect"))
    )
    (net (code "73") (name "unconnected-(Arduino1-PadA6)") (class "Default")
      (node (ref "Arduino1") (pin "A6") (pinfunction "A6_A6") (pintype "passive+no_connect"))
    )
    (net (code "74") (name "unconnected-(Arduino1-PadA7)") (class "Default")
      (node (ref "Arduino1") (pin "A7") (pinfunction "A7_A7") (pintype "passive+no_connect"))
    )
    (net (code "75") (name "unconnected-(Arduino1-PadD2)") (class "Default")
      (node (ref "Arduino1") (pin "D2") (pinfunction "D2_D2") (pintype "passive+no_connect"))
    )
    (net (code "76") (name "unconnected-(Arduino1-PadD13)") (class "Default")
      (node (ref "Arduino1") (pin "D13") (pinfunction "D13_D13") (pintype "passive+no_connect"))
    )
    (net (code "77") (name "unconnected-(Arduino1-PadREF)") (class "Default")
      (node (ref "Arduino1") (pin "REF") (pinfunction "REF_REF") (pintype "passive+no_connect"))
    )
    (net (code "78") (name "unconnected-(Arduino1-PadRST)") (class "Default")
      (node (ref "Arduino1") (pin "RST") (pinfunction "RST_RST") (pintype "passive+no_connect"))
    )
    (net (code "79") (name "unconnected-(Arduino1-PadRST)_1") (class "Default")
      (node (ref "Arduino1") (pin "RST") (pinfunction "RST_RST") (pintype "passive+no_connect"))
    )
    (net (code "80") (name "unconnected-(Arduino1-PadRX0)") (class "Default")
      (node (ref "Arduino1") (pin "RX0") (pinfunction "RX0_RX0") (pintype "passive+no_connect"))
    )
    (net (code "81") (name "unconnected-(Arduino1-PadTX1)") (class "Default")
      (node (ref "Arduino1") (pin "TX1") (pinfunction "TX1_TX1") (pintype "passive+no_connect"))
    )
    (net (code "82") (name "unconnected-(RL1-Pad2)") (class "Default")
      (node (ref "RL1") (pin "2") (pinfunction "2_2") (pintype "passive"))
    )
    (net (code "83") (name "unconnected-(RL2-Pad2)") (class "Default")
      (node (ref "RL2") (pin "2") (pinfunction "2_2") (pintype "passive"))
    )
    (net (code "84") (name "unconnected-(RL3-Pad2)") (class "Default")
      (node (ref "RL3") (pin "2") (pinfunction "2_2") (pintype "passive"))
    )
    (net (code "85") (name "unconnected-(RL4-Pad2)") (class "Default")
      (node (ref "RL4") (pin "2") (pinfunction "2_2") (pintype "passive"))
    )
    (net (code "86") (name "unconnected-(RL5-Pad2)") (class "Default")
      (node (ref "RL5") (pin "2") (pinfunction "2_2") (pintype "passive"))
    )
    (net (code "87") (name "unconnected-(U5-BAT-Pad12)") (class "Default")
      (node (ref "U5") (pin "12") (pinfunction "BAT_12") (pintype "passive+no_connect"))
    )
    (net (code "88") (name "unconnected-(U5-DS-Pad5)") (class "Default")
      (node (ref "U5") (pin "5") (pinfunction "DS_5") (pintype "passive+no_connect"))
    )
    (net (code "89") (name "unconnected-(U5-DS-Pad7)") (class "Default")
      (node (ref "U5") (pin "7") (pinfunction "DS_7") (pintype "passive+no_connect"))
    )
    (net (code "90") (name "unconnected-(U5-GND-Pad11)") (class "Default")
      (node (ref "U5") (pin "11") (pinfunction "GND_11") (pintype "passive+no_connect"))
    )
    (net (code "91") (name "unconnected-(U5-SCL-Pad8)") (class "Default")
      (node (ref "U5") (pin "8") (pinfunction "SCL_8") (pintype "passive+no_connect"))
    )
    (net (code "92") (name "unconnected-(U5-SDA-Pad9)") (class "Default")
      (node (ref "U5") (pin "9") (pinfunction "SDA_9") (pintype "passive+no_connect"))
    )
    (net (code "93") (name "unconnected-(U5-SQ-Pad6)") (class "Default")
      (node (ref "U5") (pin "6") (pinfunction "SQ_6") (pintype "passive+no_connect"))
    )
    (net (code "94") (name "unconnected-(U5-VCC-Pad10)") (class "Default")
      (node (ref "U5") (pin "10") (pinfunction "VCC_10") (pintype "passive+no_connect"))
    )
  )
)
